# flute.net
KiCad netlist of a schematic drawn in EAGLE
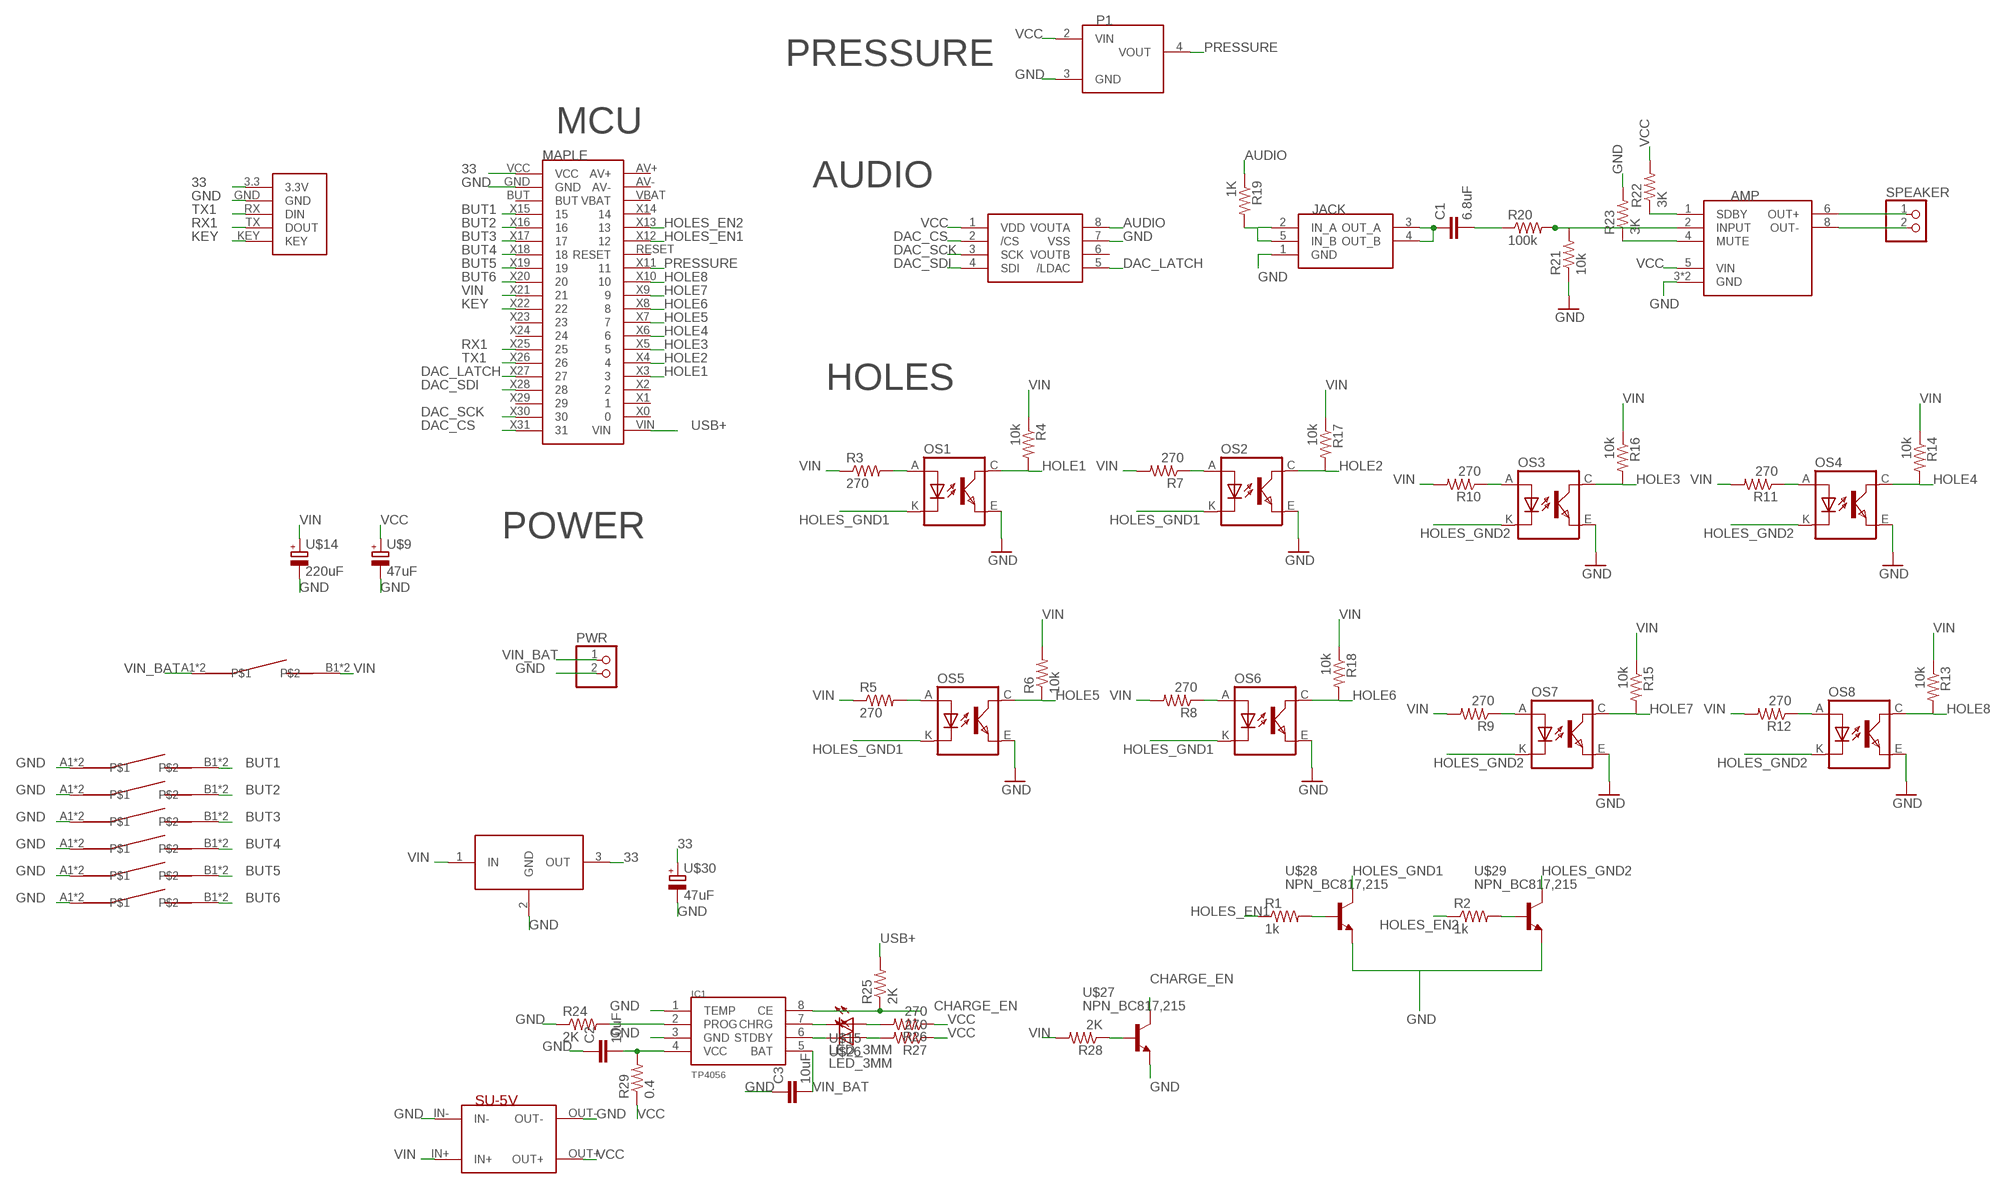
[diagram p0: schematic, sheet 1]

(export (version "E")
  (design (tool "Eeschema 10.0.6"))
  (components
    (comp (ref "AMP")
      (value "AN7511DIP8")
      (footprint "eagle-import:DIL08")
      (libsource (lib "eagle-import") (part "AN7511DIP8"))
    )
    (comp (ref "C1")
      (value "6.8uF")
      (footprint "eagle-import:0805")
      (libsource (lib "eagle-import") (part "CAP0805"))
    )
    (comp (ref "C2")
      (value "10uF")
      (footprint "eagle-import:0805")
      (libsource (lib "eagle-import") (part "CAP0805"))
    )
    (comp (ref "C3")
      (value "10uF")
      (footprint "eagle-import:0805")
      (libsource (lib "eagle-import") (part "CAP0805"))
    )
    (comp (ref "IC1")
      (value "TP4056")
      (footprint "eagle-import:SOP-8")
      (libsource (lib "eagle-import") (part "TP4056"))
    )
    (comp (ref "JACK")
      (value "JACK")
      (footprint "eagle-import:3F07")
      (libsource (lib "eagle-import") (part "JACK"))
    )
    (comp (ref "MAPLE")
      (value "MAPLE_MINI")
      (footprint "eagle-import:CONNEC_2X20")
      (libsource (lib "eagle-import") (part "MAPLE_MINI"))
    )
    (comp (ref "OS1")
      (value "TCRT5000")
      (footprint "eagle-import:TCRT5000")
      (libsource (lib "eagle-import") (part "TCRT5000"))
    )
    (comp (ref "OS2")
      (value "TCRT5000")
      (footprint "eagle-import:TCRT5000")
      (libsource (lib "eagle-import") (part "TCRT5000"))
    )
    (comp (ref "OS3")
      (value "TCRT5000")
      (footprint "eagle-import:TCRT5000")
      (libsource (lib "eagle-import") (part "TCRT5000"))
    )
    (comp (ref "OS4")
      (value "TCRT5000")
      (footprint "eagle-import:TCRT5000")
      (libsource (lib "eagle-import") (part "TCRT5000"))
    )
    (comp (ref "OS5")
      (value "TCRT5000")
      (footprint "eagle-import:TCRT5000")
      (libsource (lib "eagle-import") (part "TCRT5000"))
    )
    (comp (ref "OS6")
      (value "TCRT5000")
      (footprint "eagle-import:TCRT5000")
      (libsource (lib "eagle-import") (part "TCRT5000"))
    )
    (comp (ref "OS7")
      (value "TCRT5000")
      (footprint "eagle-import:TCRT5000")
      (libsource (lib "eagle-import") (part "TCRT5000"))
    )
    (comp (ref "OS8")
      (value "TCRT5000")
      (footprint "eagle-import:TCRT5000")
      (libsource (lib "eagle-import") (part "TCRT5000"))
    )
    (comp (ref "P1")
      (value "PRESSURE_SENSOR")
      (footprint "eagle-import:MPXV5050GP")
      (libsource (lib "eagle-import") (part "PRESSURE_SENSOR"))
    )
    (comp (ref "PWR")
      (value "CONNEC_1X02BASIC")
      (footprint "eagle-import:CONNEC_1X02")
      (libsource (lib "eagle-import") (part "CONNEC_1X02BASIC"))
    )
    (comp (ref "R1")
      (value "1k")
      (footprint "eagle-import:0805")
      (libsource (lib "eagle-import") (part "RESISTOR0805-RES"))
    )
    (comp (ref "R2")
      (value "1k")
      (footprint "eagle-import:0805")
      (libsource (lib "eagle-import") (part "RESISTOR0805-RES"))
    )
    (comp (ref "R3")
      (value "270")
      (footprint "eagle-import:0805")
      (libsource (lib "eagle-import") (part "RESISTOR0805-RES"))
    )
    (comp (ref "R4")
      (value "10k")
      (footprint "eagle-import:0805")
      (libsource (lib "eagle-import") (part "RESISTOR0805-RES"))
    )
    (comp (ref "R5")
      (value "270")
      (footprint "eagle-import:0805")
      (libsource (lib "eagle-import") (part "RESISTOR0805-RES"))
    )
    (comp (ref "R6")
      (value "10k")
      (footprint "eagle-import:0805")
      (libsource (lib "eagle-import") (part "RESISTOR0805-RES"))
    )
    (comp (ref "R7")
      (value "270")
      (footprint "eagle-import:0805")
      (libsource (lib "eagle-import") (part "RESISTOR0805-RES"))
    )
    (comp (ref "R8")
      (value "270")
      (footprint "eagle-import:0805")
      (libsource (lib "eagle-import") (part "RESISTOR0805-RES"))
    )
    (comp (ref "R9")
      (value "270")
      (footprint "eagle-import:0805")
      (libsource (lib "eagle-import") (part "RESISTOR0805-RES"))
    )
    (comp (ref "R10")
      (value "270")
      (footprint "eagle-import:0805")
      (libsource (lib "eagle-import") (part "RESISTOR0805-RES"))
    )
    (comp (ref "R11")
      (value "270")
      (footprint "eagle-import:0805")
      (libsource (lib "eagle-import") (part "RESISTOR0805-RES"))
    )
    (comp (ref "R12")
      (value "270")
      (footprint "eagle-import:0805")
      (libsource (lib "eagle-import") (part "RESISTOR0805-RES"))
    )
    (comp (ref "R13")
      (value "10k")
      (footprint "eagle-import:0805")
      (libsource (lib "eagle-import") (part "RESISTOR0805-RES"))
    )
    (comp (ref "R14")
      (value "10k")
      (footprint "eagle-import:0805")
      (libsource (lib "eagle-import") (part "RESISTOR0805-RES"))
    )
    (comp (ref "R15")
      (value "10k")
      (footprint "eagle-import:0805")
      (libsource (lib "eagle-import") (part "RESISTOR0805-RES"))
    )
    (comp (ref "R16")
      (value "10k")
      (footprint "eagle-import:0805")
      (libsource (lib "eagle-import") (part "RESISTOR0805-RES"))
    )
    (comp (ref "R17")
      (value "10k")
      (footprint "eagle-import:0805")
      (libsource (lib "eagle-import") (part "RESISTOR0805-RES"))
    )
    (comp (ref "R18")
      (value "10k")
      (footprint "eagle-import:0805")
      (libsource (lib "eagle-import") (part "RESISTOR0805-RES"))
    )
    (comp (ref "R19")
      (value "1K")
      (footprint "eagle-import:0805")
      (libsource (lib "eagle-import") (part "RESISTOR0805-RES"))
    )
    (comp (ref "R20")
      (value "100k")
      (footprint "eagle-import:0805")
      (libsource (lib "eagle-import") (part "RESISTOR0805-RES"))
    )
    (comp (ref "R21")
      (value "10k")
      (footprint "eagle-import:0805")
      (libsource (lib "eagle-import") (part "RESISTOR0805-RES"))
    )
    (comp (ref "R22")
      (value "3K")
      (footprint "eagle-import:0805")
      (libsource (lib "eagle-import") (part "RESISTOR0805-RES"))
    )
    (comp (ref "R23")
      (value "3K")
      (footprint "eagle-import:0805")
      (libsource (lib "eagle-import") (part "RESISTOR0805-RES"))
    )
    (comp (ref "R24")
      (value "2K")
      (footprint "eagle-import:0805")
      (libsource (lib "eagle-import") (part "RESISTOR0805-RES"))
    )
    (comp (ref "R25")
      (value "2K")
      (footprint "eagle-import:0805")
      (libsource (lib "eagle-import") (part "RESISTOR0805-RES"))
    )
    (comp (ref "R26")
      (value "270")
      (footprint "eagle-import:0805")
      (libsource (lib "eagle-import") (part "RESISTOR0805-RES"))
    )
    (comp (ref "R27")
      (value "270")
      (footprint "eagle-import:0805")
      (libsource (lib "eagle-import") (part "RESISTOR0805-RES"))
    )
    (comp (ref "R28")
      (value "2K")
      (footprint "eagle-import:0805")
      (libsource (lib "eagle-import") (part "RESISTOR0805-RES"))
    )
    (comp (ref "R29")
      (value "0.4")
      (footprint "eagle-import:0805")
      (libsource (lib "eagle-import") (part "RESISTOR0805-RES"))
    )
    (comp (ref "SPEAKER")
      (value "CONNEC_1X02BASIC")
      (footprint "eagle-import:CONNEC_1X02")
      (libsource (lib "eagle-import") (part "CONNEC_1X02BASIC"))
    )
    (comp (ref "SU-5V")
      (value "STEPUP-5V")
      (footprint "eagle-import:STEPUP-5V")
      (libsource (lib "eagle-import") (part "STEPUP-5V"))
    )
    (comp (ref "U$9")
      (value "47uF")
      (footprint "eagle-import:PANASONIC_D")
      (libsource (lib "eagle-import") (part "CPOL_EUPANASONIC_D"))
    )
    (comp (ref "U$14")
      (value "220uF")
      (footprint "eagle-import:PANASONIC_D8")
      (libsource (lib "eagle-import") (part "CPOL_EUPANASONIC_D8"))
    )
    (comp (ref "U$15")
      (value "LED_3MM")
      (footprint "eagle-import:LED3MM")
      (libsource (lib "eagle-import") (part "LED_3MM"))
    )
    (comp (ref "U$16")
      (value "SWITCHKCD11")
      (footprint "eagle-import:KCD11")
      (libsource (lib "eagle-import") (part "SWITCHKCD11"))
    )
    (comp (ref "U$17")
      (value "MCP4822")
      (footprint "eagle-import:DIL08")
      (libsource (lib "eagle-import") (part "RHOBAN_MCP4822"))
    )
    (comp (ref "U$18")
      (value "SWITCH6X6X10")
      (footprint "eagle-import:SWITCH_6X6X10")
      (libsource (lib "eagle-import") (part "SWITCH6X6X10"))
    )
    (comp (ref "U$19")
      (value "SWITCH6X6X10")
      (footprint "eagle-import:SWITCH_6X6X10")
      (libsource (lib "eagle-import") (part "SWITCH6X6X10"))
    )
    (comp (ref "U$20")
      (value "SWITCH6X6X10")
      (footprint "eagle-import:SWITCH_6X6X10")
      (libsource (lib "eagle-import") (part "SWITCH6X6X10"))
    )
    (comp (ref "U$21")
      (value "SWITCH6X6X10")
      (footprint "eagle-import:SWITCH_6X6X10")
      (libsource (lib "eagle-import") (part "SWITCH6X6X10"))
    )
    (comp (ref "U$22")
      (value "SWITCH6X6X10")
      (footprint "eagle-import:SWITCH_6X6X10")
      (libsource (lib "eagle-import") (part "SWITCH6X6X10"))
    )
    (comp (ref "U$23")
      (value "SWITCH6X6X10")
      (footprint "eagle-import:SWITCH_6X6X10")
      (libsource (lib "eagle-import") (part "SWITCH6X6X10"))
    )
    (comp (ref "U$24")
      (value "HC05")
      (footprint "eagle-import:HC-05")
      (libsource (lib "eagle-import") (part "HC05"))
    )
    (comp (ref "U$25")
      (value "MCP1703T-5002EDB")
      (footprint "eagle-import:SOT223")
      (libsource (lib "eagle-import") (part "MCP1703T-5002EDB"))
    )
    (comp (ref "U$26")
      (value "LED_3MM")
      (footprint "eagle-import:LED3MM")
      (libsource (lib "eagle-import") (part "LED_3MM"))
    )
    (comp (ref "U$27")
      (value "NPN_BC817,215")
      (footprint "eagle-import:SOT-23")
      (libsource (lib "eagle-import") (part "NPN_BC817,215"))
    )
    (comp (ref "U$28")
      (value "NPN_BC817,215")
      (footprint "eagle-import:SOT-23")
      (libsource (lib "eagle-import") (part "NPN_BC817,215"))
    )
    (comp (ref "U$29")
      (value "NPN_BC817,215")
      (footprint "eagle-import:SOT-23")
      (libsource (lib "eagle-import") (part "NPN_BC817,215"))
    )
    (comp (ref "U$30")
      (value "47uF")
      (footprint "eagle-import:PANASONIC_D")
      (libsource (lib "eagle-import") (part "CPOL_EUPANASONIC_D"))
    )
  )
  (nets
    (net (code "1") (name "/33") (class "Default")
      (node (ref "MAPLE") (pin "VCC") (pinfunction "VCC_VCC") (pintype "bidirectional"))
      (node (ref "U$24") (pin "3.3") (pinfunction "3.3V_3.3") (pintype "bidirectional"))
      (node (ref "U$25") (pin "3") (pinfunction "OUT_3") (pintype "bidirectional"))
      (node (ref "U$30") (pin "+") (pinfunction "+_+") (pintype "passive"))
    )
    (net (code "2") (name "/AUDIO") (class "Default")
      (node (ref "R19") (pin "1") (pinfunction "1_1") (pintype "passive"))
      (node (ref "U$17") (pin "8") (pinfunction "VOUTA_8") (pintype "bidirectional"))
    )
    (net (code "3") (name "/BUT1") (class "Default")
      (node (ref "MAPLE") (pin "X15") (pinfunction "15_X15") (pintype "bidirectional"))
      (node (ref "U$18") (pin "B1") (pinfunction "P$2_B1") (pintype "bidirectional"))
      (node (ref "U$18") (pin "B2") (pinfunction "P$2_B2") (pintype "bidirectional"))
    )
    (net (code "4") (name "/BUT2") (class "Default")
      (node (ref "MAPLE") (pin "X16") (pinfunction "16_X16") (pintype "bidirectional"))
      (node (ref "U$19") (pin "B1") (pinfunction "P$2_B1") (pintype "bidirectional"))
      (node (ref "U$19") (pin "B2") (pinfunction "P$2_B2") (pintype "bidirectional"))
    )
    (net (code "5") (name "/BUT3") (class "Default")
      (node (ref "MAPLE") (pin "X17") (pinfunction "17_X17") (pintype "bidirectional"))
      (node (ref "U$20") (pin "B1") (pinfunction "P$2_B1") (pintype "bidirectional"))
      (node (ref "U$20") (pin "B2") (pinfunction "P$2_B2") (pintype "bidirectional"))
    )
    (net (code "6") (name "/BUT4") (class "Default")
      (node (ref "MAPLE") (pin "X18") (pinfunction "18_X18") (pintype "bidirectional"))
      (node (ref "U$21") (pin "B1") (pinfunction "P$2_B1") (pintype "bidirectional"))
      (node (ref "U$21") (pin "B2") (pinfunction "P$2_B2") (pintype "bidirectional"))
    )
    (net (code "7") (name "/BUT5") (class "Default")
      (node (ref "MAPLE") (pin "X19") (pinfunction "19_X19") (pintype "bidirectional"))
      (node (ref "U$22") (pin "B1") (pinfunction "P$2_B1") (pintype "bidirectional"))
      (node (ref "U$22") (pin "B2") (pinfunction "P$2_B2") (pintype "bidirectional"))
    )
    (net (code "8") (name "/BUT6") (class "Default")
      (node (ref "MAPLE") (pin "X20") (pinfunction "20_X20") (pintype "bidirectional"))
      (node (ref "U$23") (pin "B1") (pinfunction "P$2_B1") (pintype "bidirectional"))
      (node (ref "U$23") (pin "B2") (pinfunction "P$2_B2") (pintype "bidirectional"))
    )
    (net (code "9") (name "/CHARGE_EN") (class "Default")
      (node (ref "IC1") (pin "8") (pinfunction "CE_8") (pintype "bidirectional"))
      (node (ref "R25") (pin "1") (pinfunction "1_1") (pintype "passive"))
      (node (ref "U$27") (pin "3") (pinfunction "C_3") (pintype "passive"))
    )
    (net (code "10") (name "/DAC_CS") (class "Default")
      (node (ref "MAPLE") (pin "X31") (pinfunction "31_X31") (pintype "bidirectional"))
      (node (ref "U$17") (pin "2") (pinfunction "/CS_2") (pintype "bidirectional"))
    )
    (net (code "11") (name "/DAC_LATCH") (class "Default")
      (node (ref "MAPLE") (pin "X27") (pinfunction "27_X27") (pintype "bidirectional"))
      (node (ref "U$17") (pin "5") (pinfunction "/LDAC_5") (pintype "bidirectional"))
    )
    (net (code "12") (name "/DAC_SCK") (class "Default")
      (node (ref "MAPLE") (pin "X30") (pinfunction "30_X30") (pintype "bidirectional"))
      (node (ref "U$17") (pin "3") (pinfunction "SCK_3") (pintype "bidirectional"))
    )
    (net (code "13") (name "/DAC_SDI") (class "Default")
      (node (ref "MAPLE") (pin "X28") (pinfunction "28_X28") (pintype "bidirectional"))
      (node (ref "U$17") (pin "4") (pinfunction "SDI_4") (pintype "bidirectional"))
    )
    (net (code "14") (name "/HOLE1") (class "Default")
      (node (ref "MAPLE") (pin "X3") (pinfunction "3_X3") (pintype "bidirectional"))
      (node (ref "OS1") (pin "C") (pinfunction "COLLECTOR_C") (pintype "passive"))
      (node (ref "R4") (pin "2") (pinfunction "2_2") (pintype "passive"))
    )
    (net (code "15") (name "/HOLE2") (class "Default")
      (node (ref "MAPLE") (pin "X4") (pinfunction "4_X4") (pintype "bidirectional"))
      (node (ref "OS2") (pin "C") (pinfunction "COLLECTOR_C") (pintype "passive"))
      (node (ref "R17") (pin "2") (pinfunction "2_2") (pintype "passive"))
    )
    (net (code "16") (name "/HOLE3") (class "Default")
      (node (ref "MAPLE") (pin "X5") (pinfunction "5_X5") (pintype "bidirectional"))
      (node (ref "OS3") (pin "C") (pinfunction "COLLECTOR_C") (pintype "passive"))
      (node (ref "R16") (pin "2") (pinfunction "2_2") (pintype "passive"))
    )
    (net (code "17") (name "/HOLE4") (class "Default")
      (node (ref "MAPLE") (pin "X6") (pinfunction "6_X6") (pintype "bidirectional"))
      (node (ref "OS4") (pin "C") (pinfunction "COLLECTOR_C") (pintype "passive"))
      (node (ref "R14") (pin "2") (pinfunction "2_2") (pintype "passive"))
    )
    (net (code "18") (name "/HOLE5") (class "Default")
      (node (ref "MAPLE") (pin "X7") (pinfunction "7_X7") (pintype "bidirectional"))
      (node (ref "OS5") (pin "C") (pinfunction "COLLECTOR_C") (pintype "passive"))
      (node (ref "R6") (pin "1") (pinfunction "1_1") (pintype "passive"))
    )
    (net (code "19") (name "/HOLE6") (class "Default")
      (node (ref "MAPLE") (pin "X8") (pinfunction "8_X8") (pintype "bidirectional"))
      (node (ref "OS6") (pin "C") (pinfunction "COLLECTOR_C") (pintype "passive"))
      (node (ref "R18") (pin "2") (pinfunction "2_2") (pintype "passive"))
    )
    (net (code "20") (name "/HOLE7") (class "Default")
      (node (ref "MAPLE") (pin "X9") (pinfunction "9_X9") (pintype "bidirectional"))
      (node (ref "OS7") (pin "C") (pinfunction "COLLECTOR_C") (pintype "passive"))
      (node (ref "R15") (pin "2") (pinfunction "2_2") (pintype "passive"))
    )
    (net (code "21") (name "/HOLE8") (class "Default")
      (node (ref "MAPLE") (pin "X10") (pinfunction "10_X10") (pintype "bidirectional"))
      (node (ref "OS8") (pin "C") (pinfunction "COLLECTOR_C") (pintype "passive"))
      (node (ref "R13") (pin "2") (pinfunction "2_2") (pintype "passive"))
    )
    (net (code "22") (name "/HOLES_EN1") (class "Default")
      (node (ref "MAPLE") (pin "X12") (pinfunction "12_X12") (pintype "bidirectional"))
      (node (ref "R1") (pin "1") (pinfunction "1_1") (pintype "passive"))
    )
    (net (code "23") (name "/HOLES_EN2") (class "Default")
      (node (ref "MAPLE") (pin "X13") (pinfunction "13_X13") (pintype "bidirectional"))
      (node (ref "R2") (pin "1") (pinfunction "1_1") (pintype "passive"))
    )
    (net (code "24") (name "/HOLES_GND1") (class "Default")
      (node (ref "OS1") (pin "K") (pinfunction "CATHODE_K") (pintype "passive"))
      (node (ref "OS2") (pin "K") (pinfunction "CATHODE_K") (pintype "passive"))
      (node (ref "OS5") (pin "K") (pinfunction "CATHODE_K") (pintype "passive"))
      (node (ref "OS6") (pin "K") (pinfunction "CATHODE_K") (pintype "passive"))
      (node (ref "U$28") (pin "3") (pinfunction "C_3") (pintype "passive"))
    )
    (net (code "25") (name "/HOLES_GND2") (class "Default")
      (node (ref "OS3") (pin "K") (pinfunction "CATHODE_K") (pintype "passive"))
      (node (ref "OS4") (pin "K") (pinfunction "CATHODE_K") (pintype "passive"))
      (node (ref "OS7") (pin "K") (pinfunction "CATHODE_K") (pintype "passive"))
      (node (ref "OS8") (pin "K") (pinfunction "CATHODE_K") (pintype "passive"))
      (node (ref "U$29") (pin "3") (pinfunction "C_3") (pintype "passive"))
    )
    (net (code "26") (name "/KEY") (class "Default")
      (node (ref "MAPLE") (pin "X22") (pinfunction "22_X22") (pintype "bidirectional"))
      (node (ref "U$24") (pin "KEY") (pinfunction "KEY_KEY") (pintype "bidirectional"))
    )
    (net (code "27") (name "/PRESSURE") (class "Default")
      (node (ref "MAPLE") (pin "X11") (pinfunction "11_X11") (pintype "bidirectional"))
      (node (ref "P1") (pin "4") (pinfunction "VOUT_4") (pintype "bidirectional"))
    )
    (net (code "28") (name "/RX1") (class "Default")
      (node (ref "MAPLE") (pin "X25") (pinfunction "25_X25") (pintype "bidirectional"))
      (node (ref "U$24") (pin "TX") (pinfunction "DOUT_TX") (pintype "bidirectional"))
    )
    (net (code "29") (name "/TX1") (class "Default")
      (node (ref "MAPLE") (pin "X26") (pinfunction "26_X26") (pintype "bidirectional"))
      (node (ref "U$24") (pin "RX") (pinfunction "DIN_RX") (pintype "bidirectional"))
    )
    (net (code "30") (name "/USB+") (class "Default")
      (node (ref "MAPLE") (pin "VIN") (pinfunction "VIN_VIN") (pintype "bidirectional"))
      (node (ref "R25") (pin "2") (pinfunction "2_2") (pintype "passive"))
    )
    (net (code "31") (name "/VCC") (class "Default")
      (node (ref "AMP") (pin "5") (pinfunction "VIN_5") (pintype "bidirectional"))
      (node (ref "P1") (pin "2") (pinfunction "VIN_2") (pintype "bidirectional"))
      (node (ref "R22") (pin "2") (pinfunction "2_2") (pintype "passive"))
      (node (ref "R26") (pin "1") (pinfunction "1_1") (pintype "passive"))
      (node (ref "R27") (pin "1") (pinfunction "1_1") (pintype "passive"))
      (node (ref "R29") (pin "1") (pinfunction "1_1") (pintype "passive"))
      (node (ref "SU-5V") (pin "OUT+") (pinfunction "OUT+_OUT+") (pintype "bidirectional"))
      (node (ref "U$17") (pin "1") (pinfunction "VDD_1") (pintype "bidirectional"))
      (node (ref "U$9") (pin "+") (pinfunction "+_+") (pintype "passive"))
    )
    (net (code "32") (name "/VIN") (class "Default")
      (node (ref "MAPLE") (pin "X21") (pinfunction "21_X21") (pintype "bidirectional"))
      (node (ref "R10") (pin "2") (pinfunction "2_2") (pintype "passive"))
      (node (ref "R11") (pin "2") (pinfunction "2_2") (pintype "passive"))
      (node (ref "R12") (pin "2") (pinfunction "2_2") (pintype "passive"))
      (node (ref "R13") (pin "1") (pinfunction "1_1") (pintype "passive"))
      (node (ref "R14") (pin "1") (pinfunction "1_1") (pintype "passive"))
      (node (ref "R15") (pin "1") (pinfunction "1_1") (pintype "passive"))
      (node (ref "R16") (pin "1") (pinfunction "1_1") (pintype "passive"))
      (node (ref "R17") (pin "1") (pinfunction "1_1") (pintype "passive"))
      (node (ref "R18") (pin "1") (pinfunction "1_1") (pintype "passive"))
      (node (ref "R28") (pin "2") (pinfunction "2_2") (pintype "passive"))
      (node (ref "R3") (pin "1") (pinfunction "1_1") (pintype "passive"))
      (node (ref "R4") (pin "1") (pinfunction "1_1") (pintype "passive"))
      (node (ref "R5") (pin "1") (pinfunction "1_1") (pintype "passive"))
      (node (ref "R6") (pin "2") (pinfunction "2_2") (pintype "passive"))
      (node (ref "R7") (pin "2") (pinfunction "2_2") (pintype "passive"))
      (node (ref "R8") (pin "2") (pinfunction "2_2") (pintype "passive"))
      (node (ref "R9") (pin "2") (pinfunction "2_2") (pintype "passive"))
      (node (ref "SU-5V") (pin "IN+") (pinfunction "IN+_IN+") (pintype "bidirectional"))
      (node (ref "U$14") (pin "+") (pinfunction "+_+") (pintype "passive"))
      (node (ref "U$16") (pin "B1") (pinfunction "P$2_B1") (pintype "bidirectional"))
      (node (ref "U$16") (pin "B2") (pinfunction "P$2_B2") (pintype "bidirectional"))
      (node (ref "U$25") (pin "1") (pinfunction "IN_1") (pintype "bidirectional"))
    )
    (net (code "33") (name "/VIN_BAT") (class "Default")
      (node (ref "C3") (pin "2") (pinfunction "2_2") (pintype "passive"))
      (node (ref "IC1") (pin "5") (pinfunction "BAT_5") (pintype "bidirectional"))
      (node (ref "PWR") (pin "1") (pinfunction "1_1") (pintype "passive"))
      (node (ref "U$16") (pin "A1") (pinfunction "P$1_A1") (pintype "bidirectional"))
      (node (ref "U$16") (pin "A2") (pinfunction "P$1_A2") (pintype "bidirectional"))
    )
    (net (code "34") (name "GND") (class "Default")
      (node (ref "AMP") (pin "3") (pinfunction "GND_3") (pintype "bidirectional"))
      (node (ref "AMP") (pin "7") (pinfunction "GND_7") (pintype "bidirectional"))
      (node (ref "C2") (pin "1") (pinfunction "1_1") (pintype "passive"))
      (node (ref "C3") (pin "1") (pinfunction "1_1") (pintype "passive"))
      (node (ref "IC1") (pin "1") (pinfunction "TEMP_1") (pintype "bidirectional"))
      (node (ref "IC1") (pin "3") (pinfunction "GND_3") (pintype "bidirectional"))
      (node (ref "JACK") (pin "1") (pinfunction "GND_1") (pintype "bidirectional"))
      (node (ref "MAPLE") (pin "GND") (pinfunction "GND_GND") (pintype "bidirectional"))
      (node (ref "OS1") (pin "E") (pinfunction "EMITTER_E") (pintype "passive"))
      (node (ref "OS2") (pin "E") (pinfunction "EMITTER_E") (pintype "passive"))
      (node (ref "OS3") (pin "E") (pinfunction "EMITTER_E") (pintype "passive"))
      (node (ref "OS4") (pin "E") (pinfunction "EMITTER_E") (pintype "passive"))
      (node (ref "OS5") (pin "E") (pinfunction "EMITTER_E") (pintype "passive"))
      (node (ref "OS6") (pin "E") (pinfunction "EMITTER_E") (pintype "passive"))
      (node (ref "OS7") (pin "E") (pinfunction "EMITTER_E") (pintype "passive"))
      (node (ref "OS8") (pin "E") (pinfunction "EMITTER_E") (pintype "passive"))
      (node (ref "P1") (pin "3") (pinfunction "GND_3") (pintype "bidirectional"))
      (node (ref "PWR") (pin "2") (pinfunction "2_2") (pintype "passive"))
      (node (ref "R21") (pin "1") (pinfunction "1_1") (pintype "passive"))
      (node (ref "R23") (pin "2") (pinfunction "2_2") (pintype "passive"))
      (node (ref "R24") (pin "1") (pinfunction "1_1") (pintype "passive"))
      (node (ref "SU-5V") (pin "IN-") (pinfunction "IN-_IN-") (pintype "bidirectional"))
      (node (ref "SU-5V") (pin "OUT-") (pinfunction "OUT-_OUT-") (pintype "bidirectional"))
      (node (ref "U$14") (pin "-") (pinfunction "-_-") (pintype "passive"))
      (node (ref "U$17") (pin "7") (pinfunction "VSS_7") (pintype "bidirectional"))
      (node (ref "U$18") (pin "A1") (pinfunction "P$1_A1") (pintype "bidirectional"))
      (node (ref "U$18") (pin "A2") (pinfunction "P$1_A2") (pintype "bidirectional"))
      (node (ref "U$19") (pin "A1") (pinfunction "P$1_A1") (pintype "bidirectional"))
      (node (ref "U$19") (pin "A2") (pinfunction "P$1_A2") (pintype "bidirectional"))
      (node (ref "U$20") (pin "A1") (pinfunction "P$1_A1") (pintype "bidirectional"))
      (node (ref "U$20") (pin "A2") (pinfunction "P$1_A2") (pintype "bidirectional"))
      (node (ref "U$21") (pin "A1") (pinfunction "P$1_A1") (pintype "bidirectional"))
      (node (ref "U$21") (pin "A2") (pinfunction "P$1_A2") (pintype "bidirectional"))
      (node (ref "U$22") (pin "A1") (pinfunction "P$1_A1") (pintype "bidirectional"))
      (node (ref "U$22") (pin "A2") (pinfunction "P$1_A2") (pintype "bidirectional"))
      (node (ref "U$23") (pin "A1") (pinfunction "P$1_A1") (pintype "bidirectional"))
      (node (ref "U$23") (pin "A2") (pinfunction "P$1_A2") (pintype "bidirectional"))
      (node (ref "U$24") (pin "GND") (pinfunction "GND_GND") (pintype "bidirectional"))
      (node (ref "U$25") (pin "2") (pinfunction "GND_2") (pintype "bidirectional"))
      (node (ref "U$27") (pin "2") (pinfunction "E_2") (pintype "passive"))
      (node (ref "U$28") (pin "2") (pinfunction "E_2") (pintype "passive"))
      (node (ref "U$29") (pin "2") (pinfunction "E_2") (pintype "passive"))
      (node (ref "U$30") (pin "-") (pinfunction "-_-") (pintype "passive"))
      (node (ref "U$9") (pin "-") (pinfunction "-_-") (pintype "passive"))
    )
    (net (code "35") (name "Net-(AMP-INPUT)") (class "Default")
      (node (ref "AMP") (pin "2") (pinfunction "INPUT_2") (pintype "bidirectional"))
      (node (ref "R20") (pin "2") (pinfunction "2_2") (pintype "passive"))
      (node (ref "R21") (pin "2") (pinfunction "2_2") (pintype "passive"))
    )
    (net (code "36") (name "Net-(AMP-MUTE)") (class "Default")
      (node (ref "AMP") (pin "4") (pinfunction "MUTE_4") (pintype "bidirectional"))
      (node (ref "R23") (pin "1") (pinfunction "1_1") (pintype "passive"))
    )
    (net (code "37") (name "Net-(AMP-OUT+)") (class "Default")
      (node (ref "AMP") (pin "6") (pinfunction "OUT+_6") (pintype "bidirectional"))
      (node (ref "SPEAKER") (pin "1") (pinfunction "1_1") (pintype "passive"))
    )
    (net (code "38") (name "Net-(AMP-OUT-)") (class "Default")
      (node (ref "AMP") (pin "8") (pinfunction "OUT-_8") (pintype "bidirectional"))
      (node (ref "SPEAKER") (pin "2") (pinfunction "2_2") (pintype "passive"))
    )
    (net (code "39") (name "Net-(AMP-SDBY)") (class "Default")
      (node (ref "AMP") (pin "1") (pinfunction "SDBY_1") (pintype "bidirectional"))
      (node (ref "R22") (pin "1") (pinfunction "1_1") (pintype "passive"))
    )
    (net (code "40") (name "Net-(C1-Pad2)") (class "Default")
      (node (ref "C1") (pin "2") (pinfunction "2_2") (pintype "passive"))
      (node (ref "R20") (pin "1") (pinfunction "1_1") (pintype "passive"))
    )
    (net (code "41") (name "Net-(IC1-CHRG)") (class "Default")
      (node (ref "IC1") (pin "7") (pinfunction "CHRG_7") (pintype "bidirectional"))
      (node (ref "U$15") (pin "K") (pinfunction "C_K") (pintype "passive"))
    )
    (net (code "42") (name "Net-(IC1-PROG)") (class "Default")
      (node (ref "IC1") (pin "2") (pinfunction "PROG_2") (pintype "bidirectional"))
      (node (ref "R24") (pin "2") (pinfunction "2_2") (pintype "passive"))
    )
    (net (code "43") (name "Net-(IC1-STDBY)") (class "Default")
      (node (ref "IC1") (pin "6") (pinfunction "STDBY_6") (pintype "bidirectional"))
      (node (ref "U$26") (pin "K") (pinfunction "C_K") (pintype "passive"))
    )
    (net (code "44") (name "Net-(IC1-VCC)") (class "Default")
      (node (ref "C2") (pin "2") (pinfunction "2_2") (pintype "passive"))
      (node (ref "IC1") (pin "4") (pinfunction "VCC_4") (pintype "bidirectional"))
      (node (ref "R29") (pin "2") (pinfunction "2_2") (pintype "passive"))
    )
    (net (code "45") (name "Net-(JACK-IN_A)") (class "Default")
      (node (ref "JACK") (pin "2") (pinfunction "IN_A_2") (pintype "bidirectional"))
      (node (ref "JACK") (pin "5") (pinfunction "IN_B_5") (pintype "bidirectional"))
      (node (ref "R19") (pin "2") (pinfunction "2_2") (pintype "passive"))
    )
    (net (code "46") (name "Net-(JACK-OUT_A)") (class "Default")
      (node (ref "C1") (pin "1") (pinfunction "1_1") (pintype "passive"))
      (node (ref "JACK") (pin "3") (pinfunction "OUT_A_3") (pintype "bidirectional"))
      (node (ref "JACK") (pin "4") (pinfunction "OUT_B_4") (pintype "bidirectional"))
    )
    (net (code "47") (name "Net-(OS1-ANODE)") (class "Default")
      (node (ref "OS1") (pin "A") (pinfunction "ANODE_A") (pintype "passive"))
      (node (ref "R3") (pin "2") (pinfunction "2_2") (pintype "passive"))
    )
    (net (code "48") (name "Net-(OS2-ANODE)") (class "Default")
      (node (ref "OS2") (pin "A") (pinfunction "ANODE_A") (pintype "passive"))
      (node (ref "R7") (pin "1") (pinfunction "1_1") (pintype "passive"))
    )
    (net (code "49") (name "Net-(OS3-ANODE)") (class "Default")
      (node (ref "OS3") (pin "A") (pinfunction "ANODE_A") (pintype "passive"))
      (node (ref "R10") (pin "1") (pinfunction "1_1") (pintype "passive"))
    )
    (net (code "50") (name "Net-(OS4-ANODE)") (class "Default")
      (node (ref "OS4") (pin "A") (pinfunction "ANODE_A") (pintype "passive"))
      (node (ref "R11") (pin "1") (pinfunction "1_1") (pintype "passive"))
    )
    (net (code "51") (name "Net-(OS5-ANODE)") (class "Default")
      (node (ref "OS5") (pin "A") (pinfunction "ANODE_A") (pintype "passive"))
      (node (ref "R5") (pin "2") (pinfunction "2_2") (pintype "passive"))
    )
    (net (code "52") (name "Net-(OS6-ANODE)") (class "Default")
      (node (ref "OS6") (pin "A") (pinfunction "ANODE_A") (pintype "passive"))
      (node (ref "R8") (pin "1") (pinfunction "1_1") (pintype "passive"))
    )
    (net (code "53") (name "Net-(OS7-ANODE)") (class "Default")
      (node (ref "OS7") (pin "A") (pinfunction "ANODE_A") (pintype "passive"))
      (node (ref "R9") (pin "1") (pinfunction "1_1") (pintype "passive"))
    )
    (net (code "54") (name "Net-(OS8-ANODE)") (class "Default")
      (node (ref "OS8") (pin "A") (pinfunction "ANODE_A") (pintype "passive"))
      (node (ref "R12") (pin "1") (pinfunction "1_1") (pintype "passive"))
    )
    (net (code "55") (name "Net-(R26-Pad2)") (class "Default")
      (node (ref "R26") (pin "2") (pinfunction "2_2") (pintype "passive"))
      (node (ref "U$15") (pin "A") (pinfunction "A_A") (pintype "passive"))
    )
    (net (code "56") (name "Net-(R27-Pad2)") (class "Default")
      (node (ref "R27") (pin "2") (pinfunction "2_2") (pintype "passive"))
      (node (ref "U$26") (pin "A") (pinfunction "A_A") (pintype "passive"))
    )
    (net (code "57") (name "Net-(U$27-B)") (class "Default")
      (node (ref "R28") (pin "1") (pinfunction "1_1") (pintype "passive"))
      (node (ref "U$27") (pin "1") (pinfunction "B_1") (pintype "passive"))
    )
    (net (code "58") (name "Net-(U$28-B)") (class "Default")
      (node (ref "R1") (pin "2") (pinfunction "2_2") (pintype "passive"))
      (node (ref "U$28") (pin "1") (pinfunction "B_1") (pintype "passive"))
    )
    (net (code "59") (name "Net-(U$29-B)") (class "Default")
      (node (ref "R2") (pin "2") (pinfunction "2_2") (pintype "passive"))
      (node (ref "U$29") (pin "1") (pinfunction "B_1") (pintype "passive"))
    )
    (net (code "60") (name "unconnected-(MAPLE-0-PadX0)") (class "Default")
      (node (ref "MAPLE") (pin "X0") (pinfunction "0_X0") (pintype "bidirectional"))
    )
    (net (code "61") (name "unconnected-(MAPLE-1-PadX1)") (class "Default")
      (node (ref "MAPLE") (pin "X1") (pinfunction "1_X1") (pintype "bidirectional"))
    )
    (net (code "62") (name "unconnected-(MAPLE-2-PadX2)") (class "Default")
      (node (ref "MAPLE") (pin "X2") (pinfunction "2_X2") (pintype "bidirectional"))
    )
    (net (code "63") (name "unconnected-(MAPLE-14-PadX14)") (class "Default")
      (node (ref "MAPLE") (pin "X14") (pinfunction "14_X14") (pintype "bidirectional"))
    )
    (net (code "64") (name "unconnected-(MAPLE-23-PadX23)") (class "Default")
      (node (ref "MAPLE") (pin "X23") (pinfunction "23_X23") (pintype "bidirectional"))
    )
    (net (code "65") (name "unconnected-(MAPLE-24-PadX24)") (class "Default")
      (node (ref "MAPLE") (pin "X24") (pinfunction "24_X24") (pintype "bidirectional"))
    )
    (net (code "66") (name "unconnected-(MAPLE-29-PadX29)") (class "Default")
      (node (ref "MAPLE") (pin "X29") (pinfunction "29_X29") (pintype "bidirectional"))
    )
    (net (code "67") (name "unconnected-(MAPLE-PadAV+)") (class "Default")
      (node (ref "MAPLE") (pin "AV+") (pinfunction "AV+_AV+") (pintype "bidirectional"))
    )
    (net (code "68") (name "unconnected-(MAPLE-PadAV-)") (class "Default")
      (node (ref "MAPLE") (pin "AV-") (pinfunction "AV-_AV-") (pintype "bidirectional"))
    )
    (net (code "69") (name "unconnected-(MAPLE-PadBUT)") (class "Default")
      (node (ref "MAPLE") (pin "BUT") (pinfunction "BUT_BUT") (pintype "bidirectional"))
    )
    (net (code "70") (name "unconnected-(MAPLE-PadRESET)") (class "Default")
      (node (ref "MAPLE") (pin "RESET") (pinfunction "RESET_RESET") (pintype "bidirectional"))
    )
    (net (code "71") (name "unconnected-(MAPLE-PadVBAT)") (class "Default")
      (node (ref "MAPLE") (pin "VBAT") (pinfunction "VBAT_VBAT") (pintype "bidirectional"))
    )
    (net (code "72") (name "unconnected-(U$17-VOUTB-Pad6)") (class "Default")
      (node (ref "U$17") (pin "6") (pinfunction "VOUTB_6") (pintype "bidirectional"))
    )
  )
)
